# SHT_6_I_Measure_07349-R5_L10.net
KiCad netlist of a schematic drawn in Altium Designer
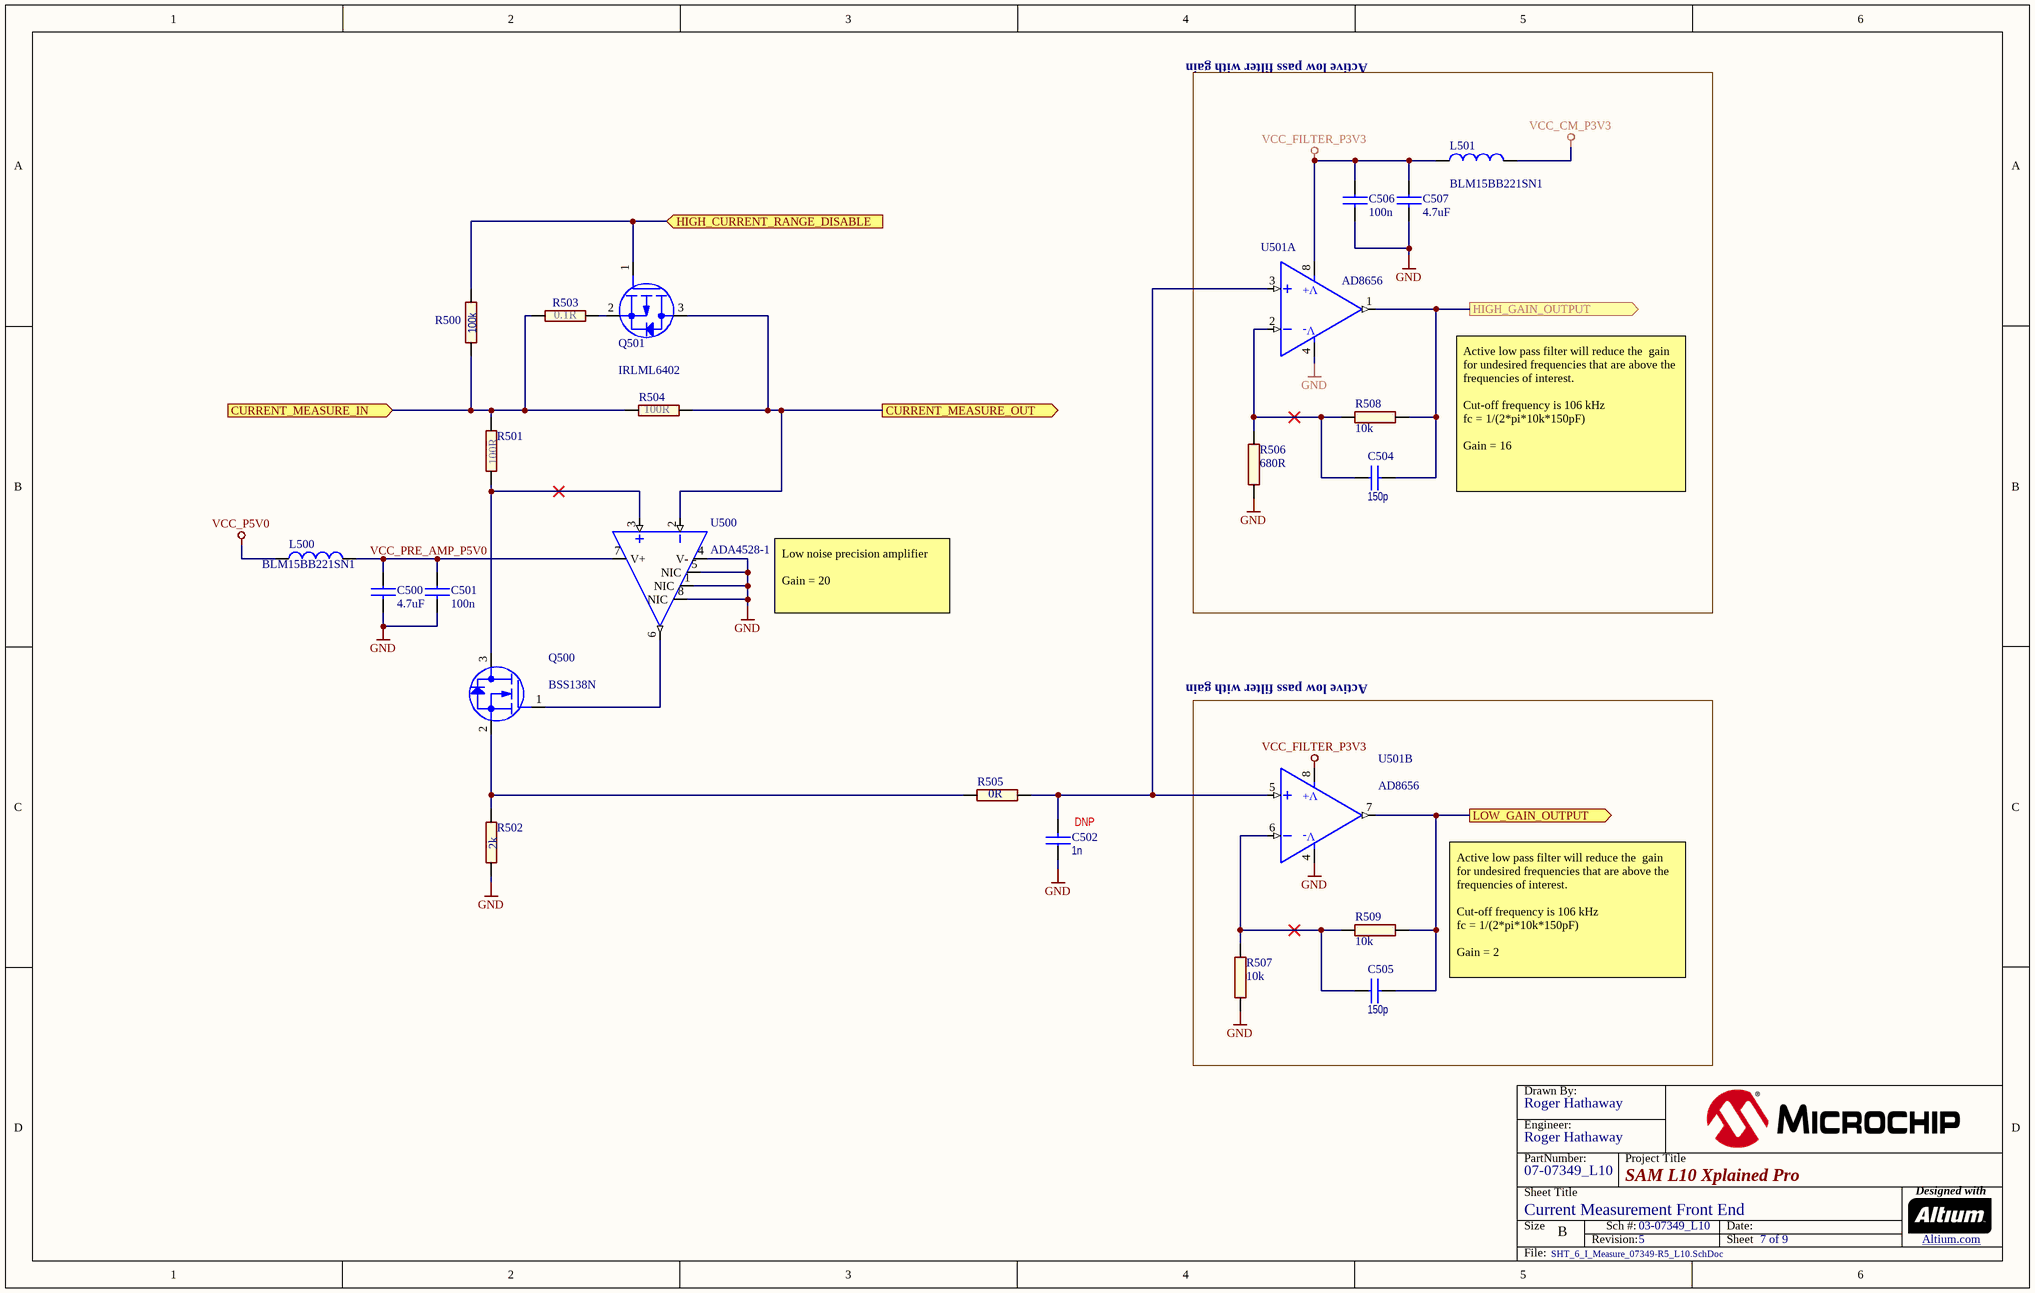
[diagram p0: SHT_6_I_Measure_07349-R5_L10.SchDoc]

(export (version "E")
  (design (tool "Eeschema 10.0.6"))
  (components
    (comp (ref "C500")
      (value "4.7uF")
      (footprint "AltiumDbLib:AP1-00117")
      (description "Ceramic capacitor, SMD 0603, X5R, 10V, 10% (de31036)")
      (fields
        (field (name "TOLERANCE") "10%")
        (field (name "MANUFACTURER") "tdk")
        (field (name "VERIFIED BY") "Lars Helge Mo")
      )
      (libsource (lib "AltiumDbLib") (part "CAP-NONPOL"))
    )
    (comp (ref "C501")
      (value "100n")
      (footprint "AltiumDbLib:AP1-00053")
      (description "Ceramic capacitor, SMD 0402, X7R, 16V, +/-10%")
      (fields
        (field (name "TOLERANCE") "16V, +/-10%")
        (field (name "MANUFACTURER") "Kemet")
        (field (name "VERIFIED BY") "Lars Helge Mo")
      )
      (libsource (lib "AltiumDbLib") (part "CAP-NONPOL"))
    )
    (comp (ref "C502")
      (value "1n")
      (footprint "AltiumDbLib:AP1-00053")
      (description "Ceramic capacitor, SMD 0402, X7R, 50V, +/-10%")
      (fields
        (field (name "TOLERANCE") "50V, +/-10%")
        (field (name "MANUFACTURER") "YAGEO CORP")
        (field (name "PLACEMENT") "DNP")
        (field (name "VERIFIED BY") "Lars Helge Mo")
      )
      (libsource (lib "AltiumDbLib") (part "CAP-NONPOL"))
    )
    (comp (ref "C504")
      (value "150p")
      (footprint "AltiumDbLib:AP1-00053")
      (description "Ceramic capacitor, SMD 0402, X7R, 50V, +/-10%")
      (fields
        (field (name "TOLERANCE") "50V, +/-10%")
        (field (name "MANUFACTURER") "YAGEO CORP")
        (field (name "VERIFIED BY") "Lars Helge Mo")
      )
      (libsource (lib "AltiumDbLib") (part "CAP-NONPOL"))
    )
    (comp (ref "C505")
      (value "150p")
      (footprint "AltiumDbLib:AP1-00053")
      (description "Ceramic capacitor, SMD 0402, X7R, 50V, +/-10%")
      (fields
        (field (name "TOLERANCE") "50V, +/-10%")
        (field (name "MANUFACTURER") "YAGEO CORP")
        (field (name "VERIFIED BY") "Lars Helge Mo")
      )
      (libsource (lib "AltiumDbLib") (part "CAP-NONPOL"))
    )
    (comp (ref "C506")
      (value "100n")
      (footprint "AltiumDbLib:AP1-00053")
      (description "Ceramic capacitor, SMD 0402, X7R, 16V, +/-10%")
      (fields
        (field (name "TOLERANCE") "16V, +/-10%")
        (field (name "MANUFACTURER") "Kemet")
        (field (name "VERIFIED BY") "Lars Helge Mo")
      )
      (libsource (lib "AltiumDbLib") (part "CAP-NONPOL"))
    )
    (comp (ref "C507")
      (value "4.7uF")
      (footprint "AltiumDbLib:AP1-00117")
      (description "Ceramic capacitor, SMD 0603, X5R, 10V, 10% (de31036)")
      (fields
        (field (name "TOLERANCE") "10%")
        (field (name "MANUFACTURER") "tdk")
        (field (name "VERIFIED BY") "Lars Helge Mo")
      )
      (libsource (lib "AltiumDbLib") (part "CAP-NONPOL"))
    )
    (comp (ref "L500")
      (value "BLM15BB221SN1")
      (footprint "AP3-00028")
      (description "SMD RF inductor 0402. Z=220Ohm (@100MHz), Max R(dc)=0.80Ohm, Max current=200mA")
      (fields
        (field (name "TOLERANCE") "±25%")
        (field (name "MANUFACTURER") "Murata")
        (field (name "VERIFIED BY") "Lars Helge Mo")
      )
      (libsource (lib "AltiumDbLib") (part "INDUCTOR"))
    )
    (comp (ref "L501")
      (value "BLM15BB221SN1")
      (footprint "AP3-00028")
      (description "SMD RF inductor 0402. Z=220Ohm (@100MHz), Max R(dc)=0.80Ohm, Max current=200mA")
      (fields
        (field (name "TOLERANCE") "±25%")
        (field (name "MANUFACTURER") "Murata")
        (field (name "VERIFIED BY") "Lars Helge Mo")
      )
      (libsource (lib "") (part "INDUCTOR_1"))
    )
    (comp (ref "Q500")
      (value "BSS138N")
      (footprint "AP5-00002")
      (fields (field (name "MANUFACTURER") "Infineon"))
      (libsource (lib "AltiumDbLib") (part "MOSFET_N_GSD"))
    )
    (comp (ref "Q501")
      (value "IRLML6402")
      (footprint "AP5-00002")
      (description "P-ch. MOSFET. -30V, -3.7A continuous,RDS(ON)=0.05Ohm@VGS=-4,5V, RDS(ON)=0.08Ohm@VGS=-2.5V")
      (fields (field (name "MANUFACTURER") "International Rectifier") (field (name "MPN") "IRLML6402PBF"))
      (libsource (lib "AltiumDbLib") (part "MOSFET_P_GSD"))
    )
    (comp (ref "R500")
      (value "100k")
      (footprint "AltiumDbLib:AP2-00011")
      (description "Thick film resistor, SMD 0402, 1/16W, 1%")
      (fields
        (field (name "TOLERANCE") "1 %")
        (field (name "MANUFACTURER") "ASJ")
        (field (name "VERIFIED BY") "Lars Helge Mo")
      )
      (libsource (lib "") (part "R2_1"))
    )
    (comp (ref "R501")
      (value "100R")
      (footprint "AltiumDbLib:AP2-00076")
      (description "ERA-3YEB101V, metal film, 100R Â±0.1%, resistor in 0603 at 100mW, TEMPCO Â±25ppm/Â°C, Max V=75V")
      (fields
        (field (name "MANUFACTURER") "Panasonic")
        (field (name "MPN") "ERA3YEB101V")
        (field (name "VERIFIED BY") "Lars Helge Mo")
      )
      (libsource (lib "") (part "R2_1"))
    )
    (comp (ref "R502")
      (value "2k")
      (footprint "AltiumDbLib:AP2-00076")
      (description "Thick film resistor, SMD 0603, 1/10W, 1%")
      (fields
        (field (name "TOLERANCE") "1 %")
        (field (name "MANUFACTURER") "YAGEO CORP")
        (field (name "VERIFIED BY") "Lars Helge Mo")
      )
      (libsource (lib "") (part "R2_1"))
    )
    (comp (ref "R503")
      (value "0.1R")
      (footprint "AltiumDbLib:AP2-00076")
      (description "WSL0603R1000FEA, metal strip resistor, 0.1 Ohm, +-1%, 0603 SMD, 1/10 W, TEMPCO +-75 ppm/Â°C")
      (fields
        (field (name "MANUFACTURER") "vishay")
        (field (name "MPN") "WSL0603R1000FEA")
        (field (name "VERIFIED BY") "Lars Helge Mo")
      )
      (libsource (lib "AltiumDbLib") (part "R2"))
    )
    (comp (ref "R504")
      (value "100R")
      (footprint "AltiumDbLib:AP2-00076")
      (description "ERA-3YEB101V, metal film, 100R Â±0.1%, resistor in 0603 at 100mW, TEMPCO Â±25ppm/Â°C, Max V=75V")
      (fields
        (field (name "MANUFACTURER") "Panasonic")
        (field (name "MPN") "ERA3YEB101V")
        (field (name "VERIFIED BY") "Lars Helge Mo")
      )
      (libsource (lib "AltiumDbLib") (part "R2"))
    )
    (comp (ref "R505")
      (value "0R")
      (footprint "AltiumDbLib:AP2-00011")
      (description "RES 0.0 OHM 1/16W 0402 SMD")
      (fields
        (field (name "TOLERANCE") "1 %")
        (field (name "MANUFACTURER") "(n/a)")
        (field (name "VERIFIED BY") "Lars Helge Mo")
      )
      (libsource (lib "") (part "R2_2"))
    )
    (comp (ref "R506")
      (value "680R")
      (footprint "AltiumDbLib:AP2-00011")
      (description "Thick film resistor, SMD 0402, 1/16W, 1%")
      (fields
        (field (name "TOLERANCE") "1 %")
        (field (name "MANUFACTURER") "ASJ")
        (field (name "VERIFIED BY") "Lars Helge Mo")
      )
      (libsource (lib "") (part "R2_1"))
    )
    (comp (ref "R507")
      (value "10k")
      (footprint "AltiumDbLib:AP2-00011")
      (description "Thick film resistor, SMD 0402, 1/16W, 1%")
      (fields
        (field (name "TOLERANCE") "1 %")
        (field (name "MANUFACTURER") "Vishay")
        (field (name "VERIFIED BY") "Lars Helge Mo")
      )
      (libsource (lib "") (part "R2_1"))
    )
    (comp (ref "R508")
      (value "10k")
      (footprint "AltiumDbLib:AP2-00011")
      (description "Thick film resistor, SMD 0402, 1/16W, 1%")
      (fields
        (field (name "TOLERANCE") "1 %")
        (field (name "MANUFACTURER") "Vishay")
        (field (name "VERIFIED BY") "Lars Helge Mo")
      )
      (libsource (lib "AltiumDbLib") (part "R2"))
    )
    (comp (ref "R509")
      (value "10k")
      (footprint "AltiumDbLib:AP2-00011")
      (description "Thick film resistor, SMD 0402, 1/16W, 1%")
      (fields
        (field (name "TOLERANCE") "1 %")
        (field (name "MANUFACTURER") "Vishay")
        (field (name "VERIFIED BY") "Lars Helge Mo")
      )
      (libsource (lib "AltiumDbLib") (part "R2"))
    )
    (comp (ref "U500")
      (value "ADA4528-1")
      (footprint "AP6-00100")
      (fields
        (field (name "MANUFACTURER") "Analog Devices")
        (field (name "MPN") "ADA4528-1ARMZ")
        (field (name "VERIFIED BY") "rmeslo")
      )
      (libsource (lib "AltiumDbLib") (part "ADA4528-1"))
    )
    (comp (ref "U501")
      (value "AD8656")
      (footprint "AP6-00100")
      (description "AD8656, dual low noise precision OpAmp, rail-to-rail, low offset 250uV, GBP 28 MHz, 8MSOP")
      (fields
        (field (name "MANUFACTURER") "Analog Devices")
        (field (name "MPN") "AD8656ARMZ")
        (field (name "VERIFIED BY") "rmeslo")
      )
      (libsource (lib "AltiumDbLib") (part "AD8656"))
    )
  )
  (nets
    (net (code "1") (name "/CURRENT_MEASURE_IN") (class "Default")
      (node (ref "R500") (pin "1") (pinfunction "1_1") (pintype "passive"))
      (node (ref "R501") (pin "2") (pinfunction "2_2") (pintype "passive"))
      (node (ref "R503") (pin "1") (pinfunction "1_1") (pintype "passive"))
      (node (ref "R504") (pin "1") (pinfunction "1_1") (pintype "passive"))
    )
    (net (code "2") (name "/CURRENT_MEASURE_OUT") (class "Default")
      (node (ref "Q501") (pin "3") (pinfunction "D_3") (pintype "passive"))
      (node (ref "R504") (pin "2") (pinfunction "2_2") (pintype "passive"))
      (node (ref "U500") (pin "2") (pinfunction "IN-_2") (pintype "input"))
    )
    (net (code "3") (name "/HIGH_CURRENT_RANGE_DISABLE") (class "Default")
      (node (ref "Q501") (pin "1") (pinfunction "G_1") (pintype "passive"))
      (node (ref "R500") (pin "2") (pinfunction "2_2") (pintype "passive"))
    )
    (net (code "4") (name "/HIGH_GAIN_OUTPUT") (class "Default")
      (node (ref "C504") (pin "2") (pinfunction "2_2") (pintype "passive"))
      (node (ref "R508") (pin "2") (pinfunction "2_2") (pintype "passive"))
      (node (ref "U501") (pin "1") (pinfunction "OUTA_1") (pintype "output"))
    )
    (net (code "5") (name "/LOW_GAIN_OUTPUT") (class "Default")
      (node (ref "C505") (pin "2") (pinfunction "2_2") (pintype "passive"))
      (node (ref "R509") (pin "2") (pinfunction "2_2") (pintype "passive"))
      (node (ref "U501") (pin "7") (pinfunction "OUTB_7") (pintype "output"))
    )
    (net (code "6") (name "/VCC_PRE_AMP_P5V0") (class "Default")
      (node (ref "C500") (pin "1") (pinfunction "1_1") (pintype "passive"))
      (node (ref "C501") (pin "1") (pinfunction "1_1") (pintype "passive"))
      (node (ref "L500") (pin "2") (pinfunction "2_2") (pintype "passive"))
      (node (ref "U500") (pin "7") (pinfunction "V+_7") (pintype "power_in"))
    )
    (net (code "7") (name "GND") (class "Default")
      (node (ref "C500") (pin "2") (pinfunction "2_2") (pintype "passive"))
      (node (ref "C501") (pin "2") (pinfunction "2_2") (pintype "passive"))
      (node (ref "C502") (pin "1") (pinfunction "1_1") (pintype "passive"))
      (node (ref "C506") (pin "2") (pinfunction "2_2") (pintype "passive"))
      (node (ref "C507") (pin "2") (pinfunction "2_2") (pintype "passive"))
      (node (ref "R502") (pin "1") (pinfunction "1_1") (pintype "passive"))
      (node (ref "R506") (pin "1") (pinfunction "1_1") (pintype "passive"))
      (node (ref "R507") (pin "1") (pinfunction "1_1") (pintype "passive"))
      (node (ref "U500") (pin "1") (pinfunction "NIC_1") (pintype "passive"))
      (node (ref "U500") (pin "4") (pinfunction "V-_4") (pintype "power_in"))
      (node (ref "U500") (pin "5") (pinfunction "NIC_5") (pintype "passive"))
      (node (ref "U500") (pin "8") (pinfunction "NIC_8") (pintype "passive"))
      (node (ref "U501") (pin "4") (pinfunction "V-_4") (pintype "power_in"))
    )
    (net (code "8") (name "Net-(Q500-D)") (class "Default")
      (node (ref "Q500") (pin "3") (pinfunction "D_3") (pintype "passive"))
      (node (ref "R501") (pin "1") (pinfunction "1_1") (pintype "passive"))
      (node (ref "U500") (pin "3") (pinfunction "IN+_3") (pintype "input"))
    )
    (net (code "9") (name "Net-(Q500-G)") (class "Default")
      (node (ref "Q500") (pin "1") (pinfunction "G_1") (pintype "passive"))
      (node (ref "U500") (pin "6") (pinfunction "OUT_6") (pintype "output"))
    )
    (net (code "10") (name "Net-(Q500-S)") (class "Default")
      (node (ref "Q500") (pin "2") (pinfunction "S_2") (pintype "passive"))
      (node (ref "R502") (pin "2") (pinfunction "2_2") (pintype "passive"))
      (node (ref "R505") (pin "2") (pinfunction "2_2") (pintype "passive"))
    )
    (net (code "11") (name "Net-(Q501-S)") (class "Default")
      (node (ref "Q501") (pin "2") (pinfunction "S_2") (pintype "passive"))
      (node (ref "R503") (pin "2") (pinfunction "2_2") (pintype "passive"))
    )
    (net (code "12") (name "Net-(U501A-INA_+)") (class "Default")
      (node (ref "C502") (pin "2") (pinfunction "2_2") (pintype "passive"))
      (node (ref "R505") (pin "1") (pinfunction "1_1") (pintype "passive"))
      (node (ref "U501") (pin "3") (pinfunction "INA_+_3") (pintype "input"))
      (node (ref "U501") (pin "5") (pinfunction "INB_+_5") (pintype "input"))
    )
    (net (code "13") (name "Net-(U501A-INA_-)") (class "Default")
      (node (ref "C504") (pin "1") (pinfunction "1_1") (pintype "passive"))
      (node (ref "R506") (pin "2") (pinfunction "2_2") (pintype "passive"))
      (node (ref "R508") (pin "1") (pinfunction "1_1") (pintype "passive"))
      (node (ref "U501") (pin "2") (pinfunction "INA_-_2") (pintype "input"))
    )
    (net (code "14") (name "Net-(U501B-INB_-)") (class "Default")
      (node (ref "C505") (pin "1") (pinfunction "1_1") (pintype "passive"))
      (node (ref "R507") (pin "2") (pinfunction "2_2") (pintype "passive"))
      (node (ref "R509") (pin "1") (pinfunction "1_1") (pintype "passive"))
      (node (ref "U501") (pin "6") (pinfunction "INB_-_6") (pintype "input"))
    )
    (net (code "15") (name "VCC_CM_P3V3") (class "Default")
      (node (ref "L501") (pin "1") (pinfunction "1_1") (pintype "passive"))
    )
    (net (code "16") (name "VCC_FILTER_P3V3") (class "Default")
      (node (ref "C506") (pin "1") (pinfunction "1_1") (pintype "passive"))
      (node (ref "C507") (pin "1") (pinfunction "1_1") (pintype "passive"))
      (node (ref "L501") (pin "2") (pinfunction "2_2") (pintype "passive"))
      (node (ref "U501") (pin "8") (pinfunction "V+_8") (pintype "power_in"))
    )
    (net (code "17") (name "VCC_P5V0") (class "Default")
      (node (ref "L500") (pin "1") (pinfunction "1_1") (pintype "passive"))
    )
  )
)
